# Sensor-VEML6070.net
KiCad netlist of a schematic drawn in EAGLE
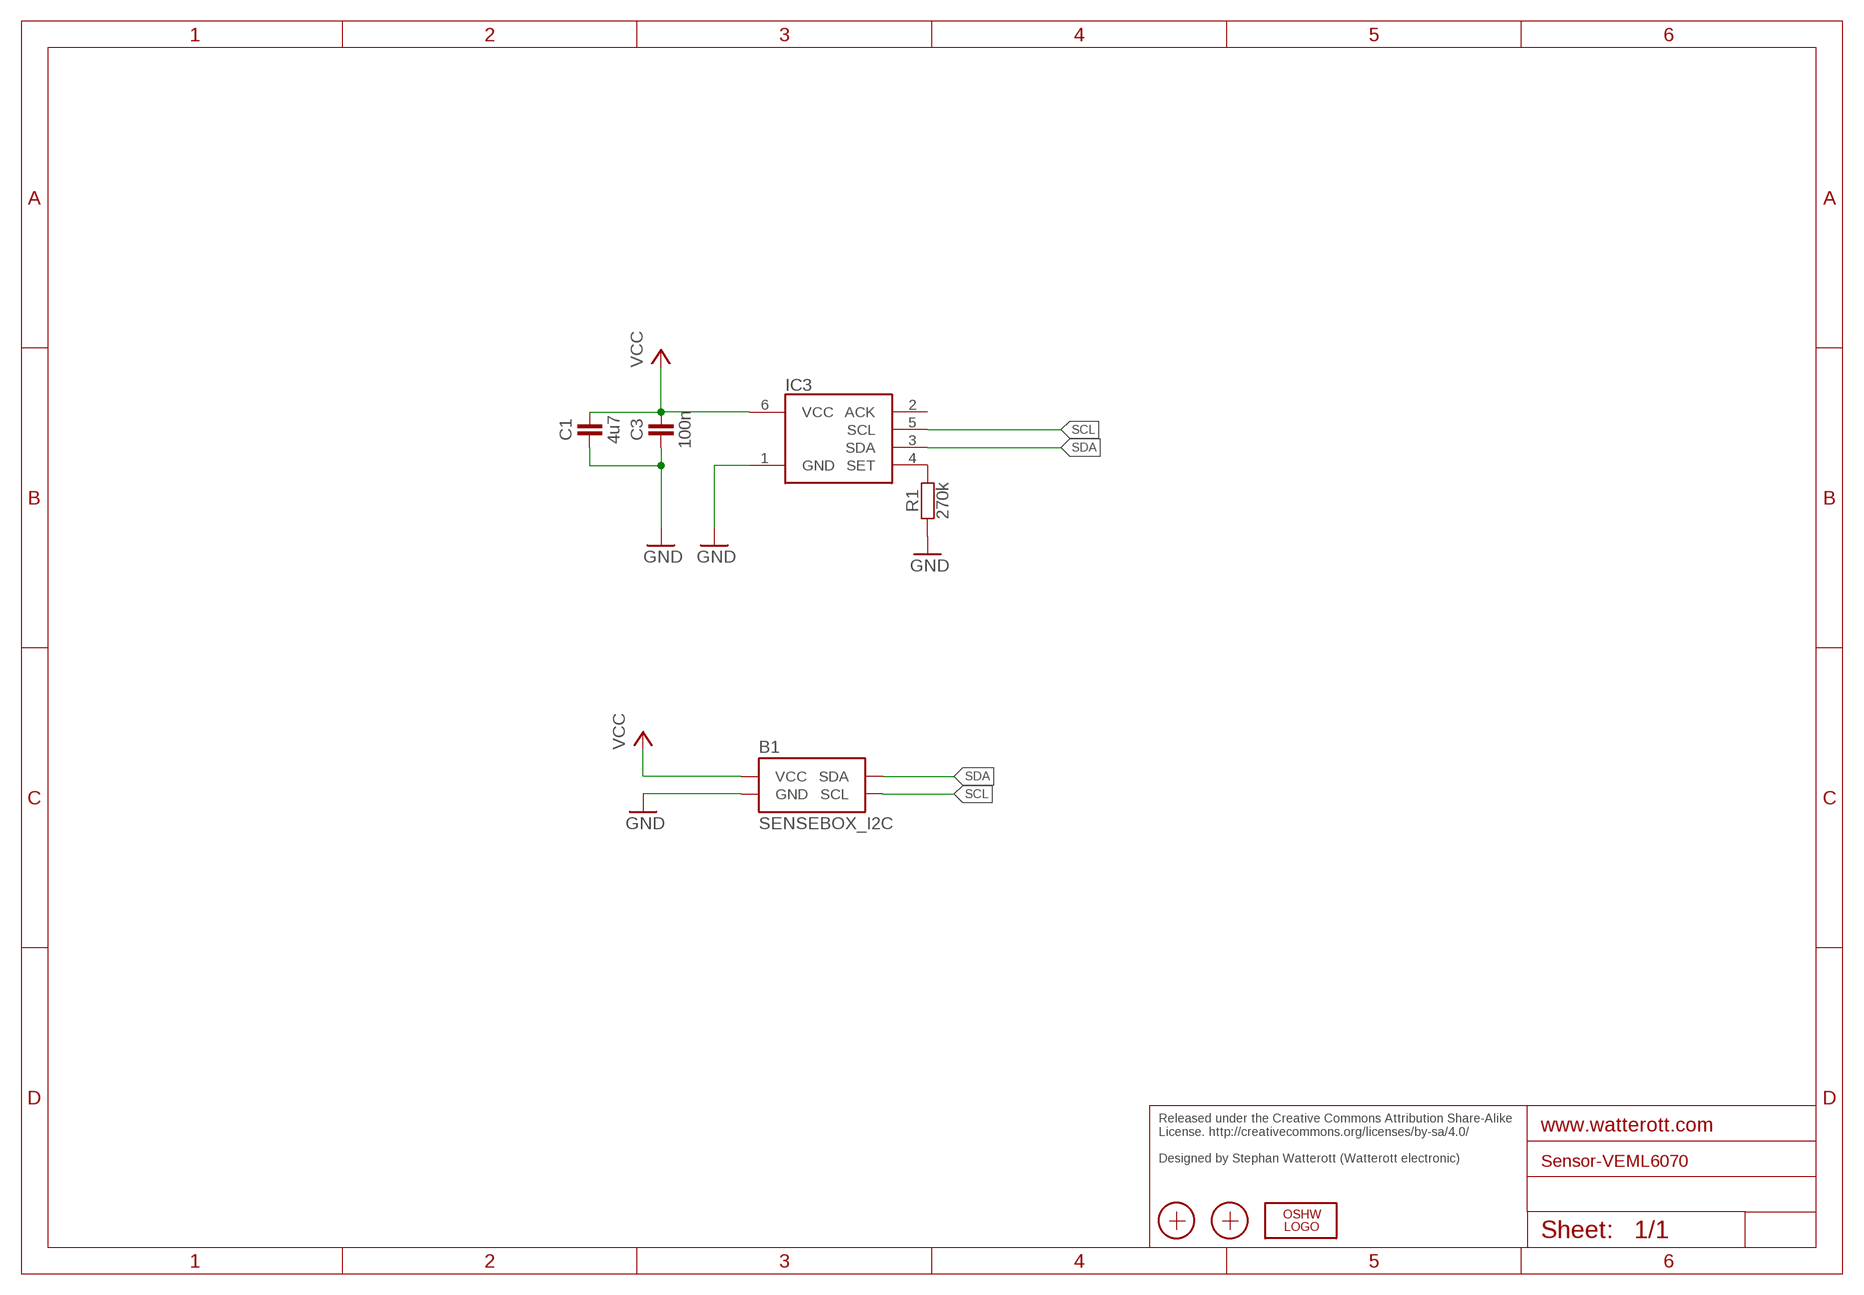
[diagram p0: schematic, sheet 1]

(export (version "E")
  (design (tool "Eeschema 10.0.6"))
  (components
    (comp (ref "B1")
      (value "SENSEBOX_I2C")
      (footprint "eagle-import:BREAKOUT_SENSEBOX_I2C")
      (libsource (lib "eagle-import") (part "SENSEBOX_I2C"))
    )
    (comp (ref "C1")
      (value "4u7")
      (footprint "eagle-import:R0402")
      (libsource (lib "eagle-import") (part "CAPACITOR-C0402"))
    )
    (comp (ref "C3")
      (value "100n")
      (footprint "eagle-import:R0402")
      (libsource (lib "eagle-import") (part "CAPACITOR-C0402"))
    )
    (comp (ref "IC3")
      (value "VEML6070")
      (footprint "eagle-import:OPLGA")
      (libsource (lib "eagle-import") (part "VEML6070"))
    )
    (comp (ref "LOGO2")
      (value "OSHW_LOGOX0070")
      (footprint "eagle-import:OSHW_6X70")
      (libsource (lib "eagle-import") (part "OSHW_LOGOX0070"))
    )
    (comp (ref "R1")
      (value "270k")
      (footprint "eagle-import:R0402")
      (libsource (lib "eagle-import") (part "RESISTOR-R0402"))
    )
    (comp (ref "X1")
      (value "PASSER-07")
      (footprint "eagle-import:PASSER_07MM")
      (libsource (lib "eagle-import") (part "PASSER-07"))
    )
    (comp (ref "X2")
      (value "PASSER-07")
      (footprint "eagle-import:PASSER_07MM")
      (libsource (lib "eagle-import") (part "PASSER-07"))
    )
  )
  (nets
    (net (code "1") (name "GND") (class "Default")
      (node (ref "B1") (pin "GND") (pinfunction "GND_GND") (pintype "power_in"))
      (node (ref "C1") (pin "1") (pinfunction "1_1") (pintype "passive"))
      (node (ref "C3") (pin "1") (pinfunction "1_1") (pintype "passive"))
      (node (ref "IC3") (pin "1") (pinfunction "GND_1") (pintype "power_in"))
      (node (ref "R1") (pin "1") (pinfunction "1_1") (pintype "passive"))
    )
    (net (code "2") (name "Net-(IC3-SET)") (class "Default")
      (node (ref "IC3") (pin "4") (pinfunction "SET_4") (pintype "bidirectional"))
      (node (ref "R1") (pin "2") (pinfunction "2_2") (pintype "passive"))
    )
    (net (code "3") (name "SCL") (class "Default")
      (node (ref "B1") (pin "SCL") (pinfunction "SCL_SCL") (pintype "bidirectional"))
      (node (ref "IC3") (pin "5") (pinfunction "SCL_5") (pintype "input"))
    )
    (net (code "4") (name "SDA") (class "Default")
      (node (ref "B1") (pin "SDA") (pinfunction "SDA_SDA") (pintype "bidirectional"))
      (node (ref "IC3") (pin "3") (pinfunction "SDA_3") (pintype "bidirectional"))
    )
    (net (code "5") (name "VCC") (class "Default")
      (node (ref "B1") (pin "VCC") (pinfunction "VCC_VCC") (pintype "power_in"))
      (node (ref "C1") (pin "2") (pinfunction "2_2") (pintype "passive"))
      (node (ref "C3") (pin "2") (pinfunction "2_2") (pintype "passive"))
      (node (ref "IC3") (pin "6") (pinfunction "VCC_6") (pintype "power_in"))
    )
    (net (code "6") (name "unconnected-(IC3-ACK-Pad2)") (class "Default")
      (node (ref "IC3") (pin "2") (pinfunction "ACK_2") (pintype "output"))
    )
  )
)
